# CAN2RPM.net
KiCad netlist of a schematic drawn in EasyEDA Pro
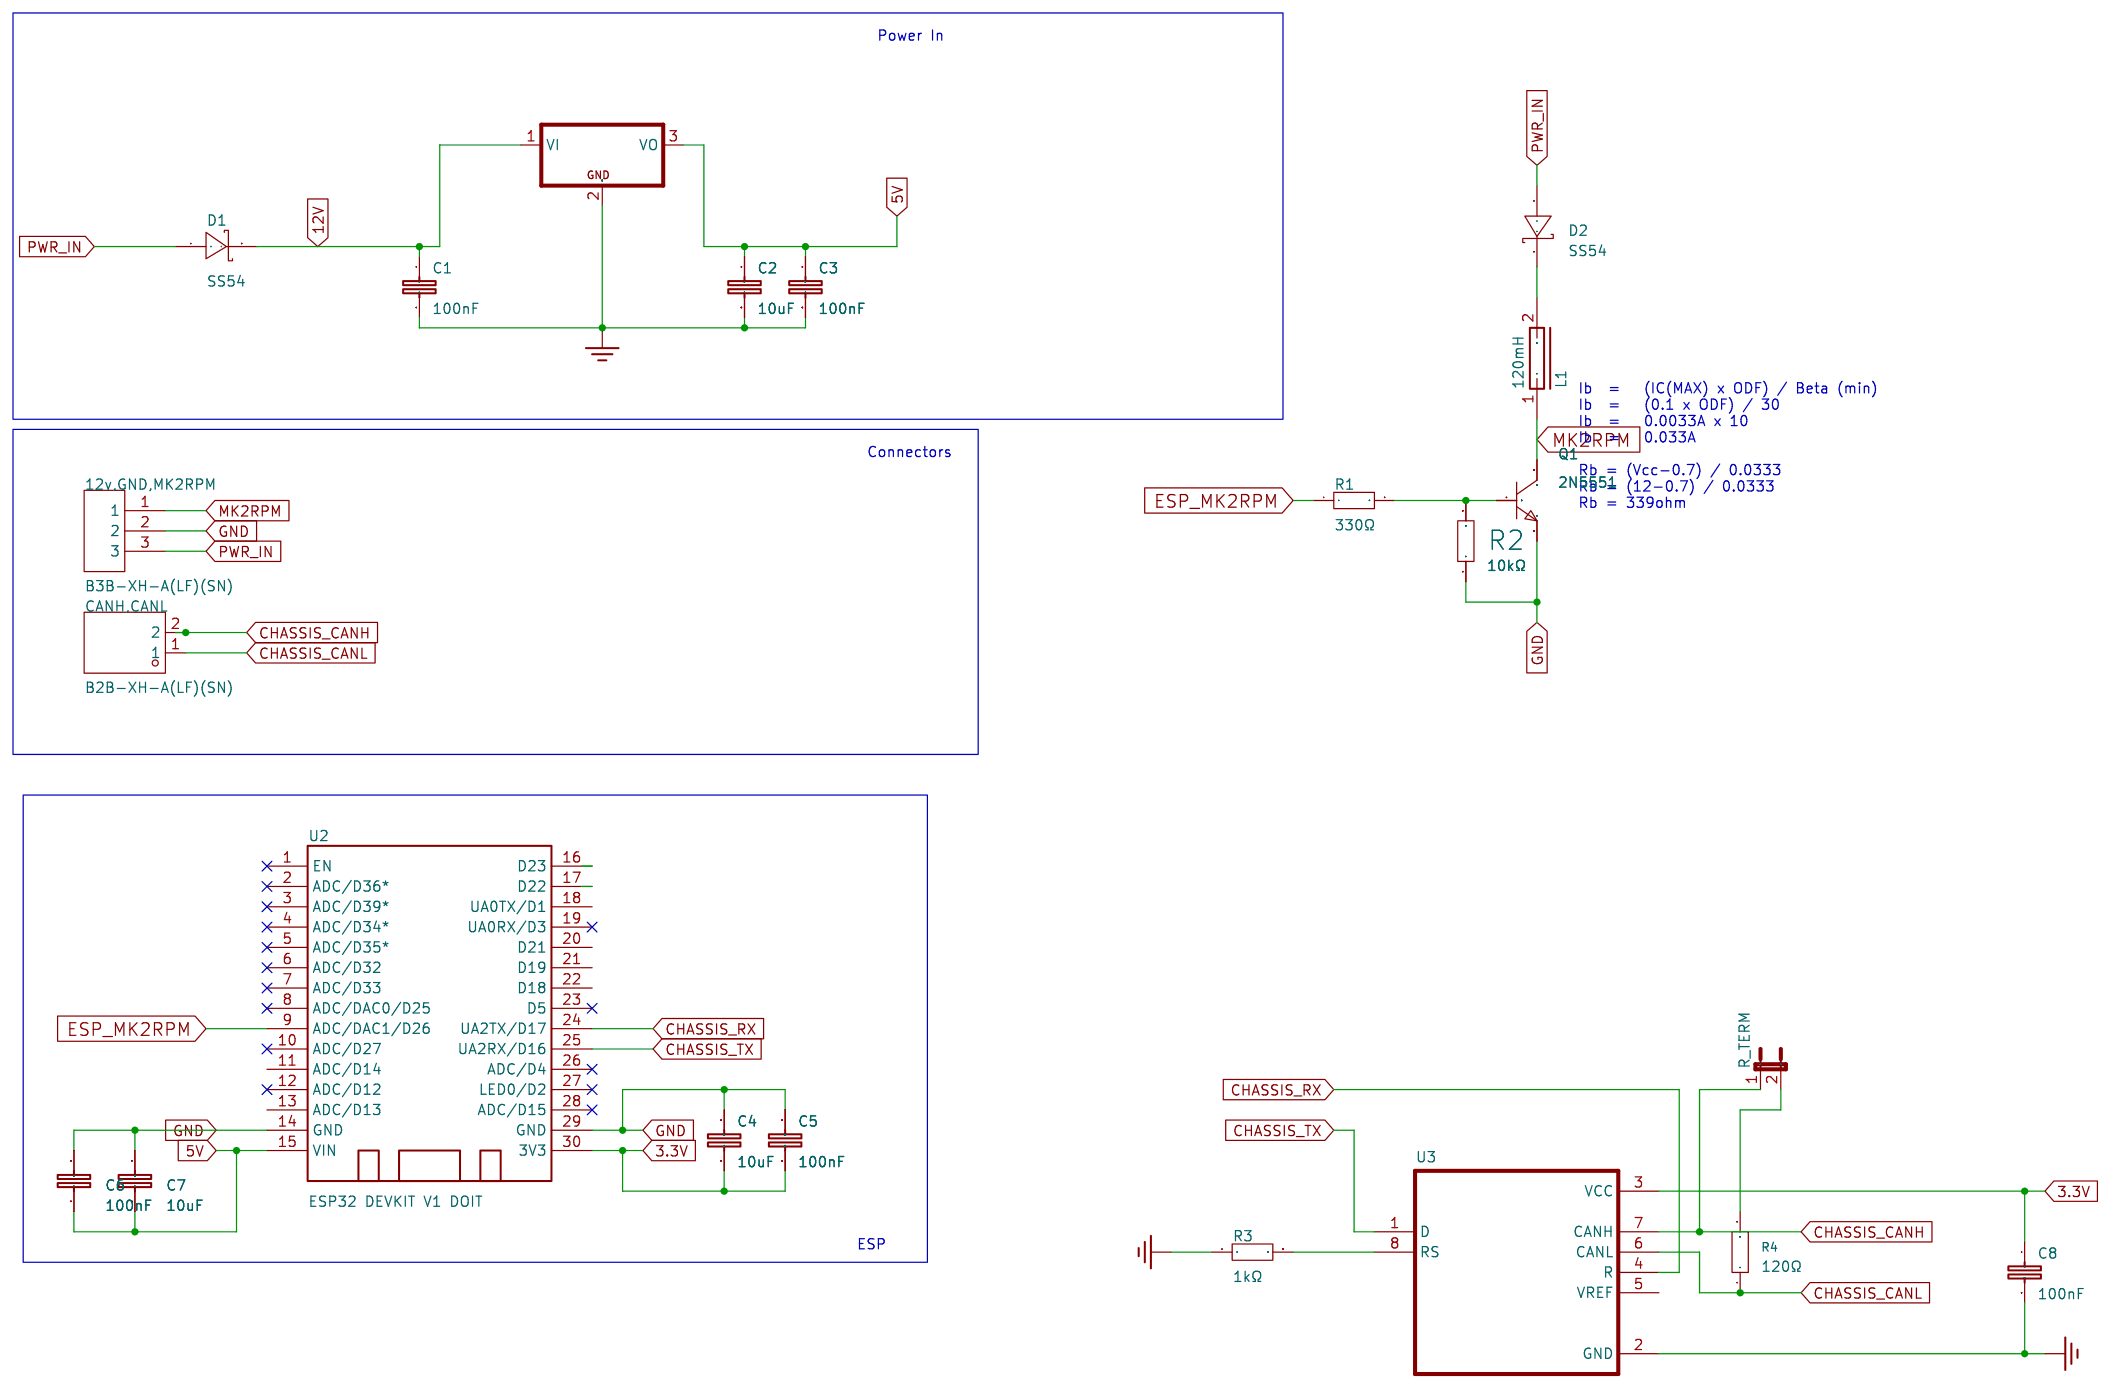
[diagram p0: schematic sheet]

(export (version "E")
  (design (tool "Eeschema 10.0.6"))
  (components
    (comp (ref "12v,GND,MK2RPM")
      (value "B3B-XH-A(LF)(SN)")
      (footprint "easyedapro:CONN-TH_3P-P2.50_A2501WV2-3P")
      (fields (field (name "Manufacturer") "JST"))
      (libsource (lib "easyedapro") (part "B3B-XH-A(LF)(SN)"))
    )
    (comp (ref "C1")
      (value "100nF")
      (description "Capacitance:100nF Tolerance:±10% Tolerance:±10% Voltage Rating:50V Temperature Coefficient:-")
      (fields
        (field (name "Manufacturer Part") "CT41G-0805-2X1-50V-0.1μF-K(N)")
        (field (name "Manufacturer") "TORCH(火炬)")
      )
      (libsource (lib "easyedapro") (part "capacitor-wima_C_2.5/2"))
    )
    (comp (ref "C2")
      (value "10uF")
      (fields
        (field (name "Manufacturer Part") "CL21A106KAYNNNE")
        (field (name "Manufacturer") "SAMSUNG(三星)")
      )
      (libsource (lib "easyedapro") (part "capacitor-wima_C_2.5/2"))
    )
    (comp (ref "C3")
      (value "100nF")
      (description "Capacitance:100nF Tolerance:±10% Tolerance:±10% Voltage Rating:50V Temperature Coefficient:-")
      (fields
        (field (name "Manufacturer Part") "CT41G-0805-2X1-50V-0.1μF-K(N)")
        (field (name "Manufacturer") "TORCH(火炬)")
      )
      (libsource (lib "easyedapro") (part "capacitor-wima_C_2.5/2"))
    )
    (comp (ref "C4")
      (value "10uF")
      (fields
        (field (name "Manufacturer Part") "CL21A106KAYNNNE")
        (field (name "Manufacturer") "SAMSUNG(三星)")
      )
      (libsource (lib "easyedapro") (part "capacitor-wima_C_2.5/2"))
    )
    (comp (ref "C5")
      (value "100nF")
      (description "Capacitance:100nF Tolerance:±10% Tolerance:±10% Voltage Rating:50V Temperature Coefficient:X7R")
      (fields
        (field (name "Manufacturer Part") "CC0603KRX7R9BB104")
        (field (name "Manufacturer") "YAGEO(国巨)")
      )
      (libsource (lib "easyedapro") (part "capacitor-wima_C_2.5/2"))
    )
    (comp (ref "C6")
      (value "100nF")
      (description "Capacitance:100nF Tolerance:±10% Tolerance:±10% Voltage Rating:50V Temperature Coefficient:X7R")
      (fields
        (field (name "Manufacturer Part") "CC0603KRX7R9BB104")
        (field (name "Manufacturer") "YAGEO(国巨)")
      )
      (libsource (lib "easyedapro") (part "capacitor-wima_C_2.5/2"))
    )
    (comp (ref "C7")
      (value "10uF")
      (fields
        (field (name "Manufacturer Part") "CL21A106KAYNNNE")
        (field (name "Manufacturer") "SAMSUNG(三星)")
      )
      (libsource (lib "easyedapro") (part "capacitor-wima_C_2.5/2"))
    )
    (comp (ref "C8")
      (value "100nF")
      (description "Capacitance:100nF Tolerance:±10% Tolerance:±10% Voltage Rating:50V Temperature Coefficient:-")
      (fields
        (field (name "Manufacturer Part") "CT41G-0805-2X1-50V-0.1μF-K(N)")
        (field (name "Manufacturer") "TORCH(火炬)")
      )
      (libsource (lib "easyedapro") (part "capacitor-wima_C_2.5/2"))
    )
    (comp (ref "CANH,CANL")
      (value "B2B-XH-A(LF)(SN)")
      (footprint "easyedapro:CONN-TH_B2B-XH-A-LF-SN")
      (fields (field (name "Manufacturer") "JST"))
      (libsource (lib "easyedapro") (part "B2B-XH-A (LF)(SN)"))
    )
    (comp (ref "D1")
      (value "SS54")
      (footprint "easyedapro:SMA_L4.4-W2.8-LS5.4-R-RD")
      (fields (field (name "Manufacturer") "MDD(辰达半导体)"))
      (libsource (lib "easyedapro") (part "SS54_C22452"))
    )
    (comp (ref "D2")
      (value "SS54")
      (footprint "easyedapro:SMA_L4.4-W2.8-LS5.4-R-RD")
      (fields (field (name "Manufacturer") "MDD(辰达半导体)"))
      (libsource (lib "easyedapro") (part "SS54_C22452"))
    )
    (comp (ref "IC1")
      (value "L7805ABD2T-TR")
      (fields (field (name "Manufacturer") "ST(意法半导体)"))
      (libsource (lib "easyedapro") (part "linear_78*_TV"))
    )
    (comp (ref "L1")
      (value "120mH")
      (fields (field (name "Manufacturer Part") "DR125-124-R") (field (name "Manufacturer") "EATON(伊顿)"))
      (libsource (lib "easyedapro") (part "DR125_DR125_"))
    )
    (comp (ref "Q1")
      (value "2N5551")
      (footprint "easyedapro:SOT-23-3_L2.9-W1.4-P1.90-LS2.5-BR")
      (fields (field (name "Manufacturer") "RUILON(瑞隆源)"))
      (libsource (lib "easyedapro") (part "2N5551_C7529570"))
    )
    (comp (ref "R1")
      (value "330Ω")
      (footprint "easyedapro:R0603")
      (fields
        (field (name "Manufacturer Part") "0603WAF3300T5E")
        (field (name "Manufacturer") "UNI-ROYAL(厚声)")
      )
      (libsource (lib "easyedapro") (part "0603WAF3300T5E"))
    )
    (comp (ref "R2")
      (value "10kΩ")
      (footprint "easyedapro:R0603")
      (fields
        (field (name "Manufacturer Part") "0603WAF1002T5E")
        (field (name "Manufacturer") "UNI-ROYAL(厚声)")
      )
      (libsource (lib "easyedapro") (part "0603WAF1002T5E"))
    )
    (comp (ref "R3")
      (value "1kΩ")
      (footprint "easyedapro:R0603")
      (fields
        (field (name "Manufacturer Part") "0603WAF1001T5E")
        (field (name "Manufacturer") "UNI-ROYAL(厚声)")
      )
      (libsource (lib "easyedapro") (part "0603WAF1001T5E"))
    )
    (comp (ref "R4")
      (value "120Ω")
      (footprint "easyedapro:R0603")
      (fields
        (field (name "Manufacturer Part") "0603WAF1200T5E")
        (field (name "Manufacturer") "UNI-ROYAL(厚声)")
      )
      (libsource (lib "easyedapro") (part "0603WAF1200T5E"))
    )
    (comp (ref "R_TERM")
      (value "PZ254V-11-02P")
      (fields (field (name "Manufacturer") "XFCN(兴飞)"))
      (libsource (lib "easyedapro") (part "jumper_JP1E_"))
    )
    (comp (ref "U2")
      (value "ESP32 DEVKIT V1 DOIT")
      (footprint "easyedapro:DOIT-ESP32-DEVKIT-V1")
      (libsource (lib "easyedapro") (part "ESP32 DEVKIT V1 DOIT"))
    )
    (comp (ref "U3")
      (value "SN65HVD230DR")
      (fields (field (name "Manufacturer") "TI(德州仪器)"))
      (libsource (lib "easyedapro") (part "SN65HVD230DR_SN65HVD230DR_"))
    )
  )
  (nets
    (net (code "1") (name "3.3V") (class "Default")
      (node (ref "C4") (pin "2") (pinfunction "2_2") (pintype "unspecified"))
      (node (ref "C5") (pin "2") (pinfunction "2_2") (pintype "unspecified"))
      (node (ref "C8") (pin "1") (pinfunction "1_1") (pintype "unspecified"))
      (node (ref "U2") (pin "30") (pinfunction "3V3_30") (pintype "bidirectional"))
      (node (ref "U3") (pin "3") (pinfunction "VCC_3") (pintype "unspecified"))
    )
    (net (code "2") (name "5V") (class "Default")
      (node (ref "C2") (pin "1") (pinfunction "1_1") (pintype "unspecified"))
      (node (ref "C3") (pin "1") (pinfunction "1_1") (pintype "unspecified"))
      (node (ref "C6") (pin "1") (pinfunction "1_1") (pintype "unspecified"))
      (node (ref "C7") (pin "1") (pinfunction "1_1") (pintype "unspecified"))
      (node (ref "IC1") (pin "3") (pinfunction "VO_3") (pintype "unspecified"))
      (node (ref "U2") (pin "15") (pinfunction "VIN_15") (pintype "input"))
    )
    (net (code "3") (name "12V") (class "Default")
      (node (ref "C1") (pin "1") (pinfunction "1_1") (pintype "unspecified"))
      (node (ref "D1") (pin "2") (pinfunction "K_2") (pintype "unspecified"))
      (node (ref "IC1") (pin "1") (pinfunction "VI_1") (pintype "input"))
    )
    (net (code "4") (name "CHASSIS_CANH") (class "Default")
      (node (ref "CANH,CANL") (pin "2") (pinfunction "2_2") (pintype "unspecified"))
      (node (ref "R_TERM") (pin "1") (pinfunction "1_1") (pintype "unspecified"))
      (node (ref "U3") (pin "7") (pinfunction "CANH_7") (pintype "output"))
    )
    (net (code "5") (name "CHASSIS_CANL") (class "Default")
      (node (ref "CANH,CANL") (pin "1") (pinfunction "1_1") (pintype "unspecified"))
      (node (ref "R4") (pin "1") (pinfunction "1_1") (pintype "input"))
      (node (ref "U3") (pin "6") (pinfunction "CANL_6") (pintype "output"))
    )
    (net (code "6") (name "CHASSIS_RX") (class "Default")
      (node (ref "U2") (pin "24") (pinfunction "UA2TX/D17_24") (pintype "bidirectional"))
      (node (ref "U3") (pin "4") (pinfunction "R_4") (pintype "output"))
    )
    (net (code "7") (name "CHASSIS_TX") (class "Default")
      (node (ref "U2") (pin "25") (pinfunction "UA2RX/D16_25") (pintype "bidirectional"))
      (node (ref "U3") (pin "1") (pinfunction "D_1") (pintype "input"))
    )
    (net (code "8") (name "ESP_MK2RPM") (class "Default")
      (node (ref "R1") (pin "1") (pinfunction "1_1") (pintype "input"))
      (node (ref "U2") (pin "9") (pinfunction "ADC/DAC1/D26_9") (pintype "bidirectional"))
    )
    (net (code "9") (name "GND") (class "Default")
      (node (ref "12v,GND,MK2RPM") (pin "2") (pinfunction "2_2") (pintype "unspecified"))
      (node (ref "C1") (pin "2") (pinfunction "2_2") (pintype "unspecified"))
      (node (ref "C2") (pin "2") (pinfunction "2_2") (pintype "unspecified"))
      (node (ref "C3") (pin "2") (pinfunction "2_2") (pintype "unspecified"))
      (node (ref "C4") (pin "1") (pinfunction "1_1") (pintype "unspecified"))
      (node (ref "C5") (pin "1") (pinfunction "1_1") (pintype "unspecified"))
      (node (ref "C6") (pin "2") (pinfunction "2_2") (pintype "unspecified"))
      (node (ref "C7") (pin "2") (pinfunction "2_2") (pintype "unspecified"))
      (node (ref "C8") (pin "2") (pinfunction "2_2") (pintype "unspecified"))
      (node (ref "IC1") (pin "2") (pinfunction "GND_2") (pintype "unspecified"))
      (node (ref "Q1") (pin "2") (pinfunction "E_2") (pintype "unspecified"))
      (node (ref "R2") (pin "1") (pinfunction "1_1") (pintype "input"))
      (node (ref "R3") (pin "1") (pinfunction "1_1") (pintype "input"))
      (node (ref "U2") (pin "14") (pinfunction "GND_14") (pintype "bidirectional"))
      (node (ref "U2") (pin "29") (pinfunction "GND_29") (pintype "bidirectional"))
      (node (ref "U3") (pin "2") (pinfunction "GND_2") (pintype "unspecified"))
    )
    (net (code "10") (name "MK2RPM") (class "Default")
      (node (ref "12v,GND,MK2RPM") (pin "1") (pinfunction "1_1") (pintype "unspecified"))
      (node (ref "L1") (pin "1") (pinfunction "1_1") (pintype "unspecified"))
      (node (ref "Q1") (pin "3") (pinfunction "C_3") (pintype "unspecified"))
    )
    (net (code "11") (name "Net-(D2-K)") (class "Default")
      (node (ref "D2") (pin "2") (pinfunction "K_2") (pintype "unspecified"))
      (node (ref "L1") (pin "2") (pinfunction "2_2") (pintype "unspecified"))
    )
    (net (code "12") (name "Net-(Q1-B)") (class "Default")
      (node (ref "Q1") (pin "1") (pinfunction "B_1") (pintype "unspecified"))
      (node (ref "R1") (pin "2") (pinfunction "2_2") (pintype "input"))
      (node (ref "R2") (pin "2") (pinfunction "2_2") (pintype "input"))
    )
    (net (code "13") (name "Net-(R4-Pad2)") (class "Default")
      (node (ref "R4") (pin "2") (pinfunction "2_2") (pintype "input"))
      (node (ref "R_TERM") (pin "2") (pinfunction "2_2") (pintype "unspecified"))
    )
    (net (code "14") (name "Net-(U3-RS)") (class "Default")
      (node (ref "R3") (pin "2") (pinfunction "2_2") (pintype "input"))
      (node (ref "U3") (pin "8") (pinfunction "RS_8") (pintype "input"))
    )
    (net (code "15") (name "PWR_IN") (class "Default")
      (node (ref "12v,GND,MK2RPM") (pin "3") (pinfunction "3_3") (pintype "unspecified"))
      (node (ref "D1") (pin "1") (pinfunction "A_1") (pintype "unspecified"))
      (node (ref "D2") (pin "1") (pinfunction "A_1") (pintype "unspecified"))
    )
    (net (code "16") (name "unconnected-(U2-ADC{slash}D4-Pad26)") (class "Default")
      (node (ref "U2") (pin "26") (pinfunction "ADC/D4_26") (pintype "bidirectional+no_connect"))
    )
    (net (code "17") (name "unconnected-(U2-ADC{slash}D12-Pad12)") (class "Default")
      (node (ref "U2") (pin "12") (pinfunction "ADC/D12_12") (pintype "bidirectional+no_connect"))
    )
    (net (code "18") (name "unconnected-(U2-ADC{slash}D13-Pad13)") (class "Default")
      (node (ref "U2") (pin "13") (pinfunction "ADC/D13_13") (pintype "bidirectional"))
    )
    (net (code "19") (name "unconnected-(U2-ADC{slash}D14-Pad11)") (class "Default")
      (node (ref "U2") (pin "11") (pinfunction "ADC/D14_11") (pintype "bidirectional"))
    )
    (net (code "20") (name "unconnected-(U2-ADC{slash}D15-Pad28)") (class "Default")
      (node (ref "U2") (pin "28") (pinfunction "ADC/D15_28") (pintype "bidirectional+no_connect"))
    )
    (net (code "21") (name "unconnected-(U2-ADC{slash}D27-Pad10)") (class "Default")
      (node (ref "U2") (pin "10") (pinfunction "ADC/D27_10") (pintype "bidirectional+no_connect"))
    )
    (net (code "22") (name "unconnected-(U2-ADC{slash}D32-Pad6)") (class "Default")
      (node (ref "U2") (pin "6") (pinfunction "ADC/D32_6") (pintype "bidirectional+no_connect"))
    )
    (net (code "23") (name "unconnected-(U2-ADC{slash}D33-Pad7)") (class "Default")
      (node (ref "U2") (pin "7") (pinfunction "ADC/D33_7") (pintype "bidirectional+no_connect"))
    )
    (net (code "24") (name "unconnected-(U2-ADC{slash}D34*-Pad4)") (class "Default")
      (node (ref "U2") (pin "4") (pinfunction "ADC/D34*_4") (pintype "input+no_connect"))
    )
    (net (code "25") (name "unconnected-(U2-ADC{slash}D35*-Pad5)") (class "Default")
      (node (ref "U2") (pin "5") (pinfunction "ADC/D35*_5") (pintype "input+no_connect"))
    )
    (net (code "26") (name "unconnected-(U2-ADC{slash}D36*-Pad2)") (class "Default")
      (node (ref "U2") (pin "2") (pinfunction "ADC/D36*_2") (pintype "input+no_connect"))
    )
    (net (code "27") (name "unconnected-(U2-ADC{slash}D39*-Pad3)") (class "Default")
      (node (ref "U2") (pin "3") (pinfunction "ADC/D39*_3") (pintype "input+no_connect"))
    )
    (net (code "28") (name "unconnected-(U2-ADC{slash}DAC0{slash}D25-Pad8)") (class "Default")
      (node (ref "U2") (pin "8") (pinfunction "ADC/DAC0/D25_8") (pintype "bidirectional+no_connect"))
    )
    (net (code "29") (name "unconnected-(U2-D5-Pad23)") (class "Default")
      (node (ref "U2") (pin "23") (pinfunction "D5_23") (pintype "bidirectional+no_connect"))
    )
    (net (code "30") (name "unconnected-(U2-D18-Pad22)") (class "Default")
      (node (ref "U2") (pin "22") (pinfunction "D18_22") (pintype "bidirectional"))
    )
    (net (code "31") (name "unconnected-(U2-D19-Pad21)") (class "Default")
      (node (ref "U2") (pin "21") (pinfunction "D19_21") (pintype "bidirectional"))
    )
    (net (code "32") (name "unconnected-(U2-D21-Pad20)") (class "Default")
      (node (ref "U2") (pin "20") (pinfunction "D21_20") (pintype "bidirectional"))
    )
    (net (code "33") (name "unconnected-(U2-D22-Pad17)") (class "Default")
      (node (ref "U2") (pin "17") (pinfunction "D22_17") (pintype "bidirectional"))
    )
    (net (code "34") (name "unconnected-(U2-D23-Pad16)") (class "Default")
      (node (ref "U2") (pin "16") (pinfunction "D23_16") (pintype "bidirectional"))
    )
    (net (code "35") (name "unconnected-(U2-EN-Pad1)") (class "Default")
      (node (ref "U2") (pin "1") (pinfunction "EN_1") (pintype "bidirectional+no_connect"))
    )
    (net (code "36") (name "unconnected-(U2-LED0{slash}D2-Pad27)") (class "Default")
      (node (ref "U2") (pin "27") (pinfunction "LED0/D2_27") (pintype "bidirectional+no_connect"))
    )
    (net (code "37") (name "unconnected-(U2-UA0RX{slash}D3-Pad19)") (class "Default")
      (node (ref "U2") (pin "19") (pinfunction "UA0RX/D3_19") (pintype "bidirectional+no_connect"))
    )
    (net (code "38") (name "unconnected-(U2-UA0TX{slash}D1-Pad18)") (class "Default")
      (node (ref "U2") (pin "18") (pinfunction "UA0TX/D1_18") (pintype "bidirectional"))
    )
    (net (code "39") (name "unconnected-(U3-VREF-Pad5)") (class "Default")
      (node (ref "U3") (pin "5") (pinfunction "VREF_5") (pintype "output"))
    )
  )
)
